# Grove_-_Joint_v2_0.net
KiCad netlist of a schematic drawn in EAGLE
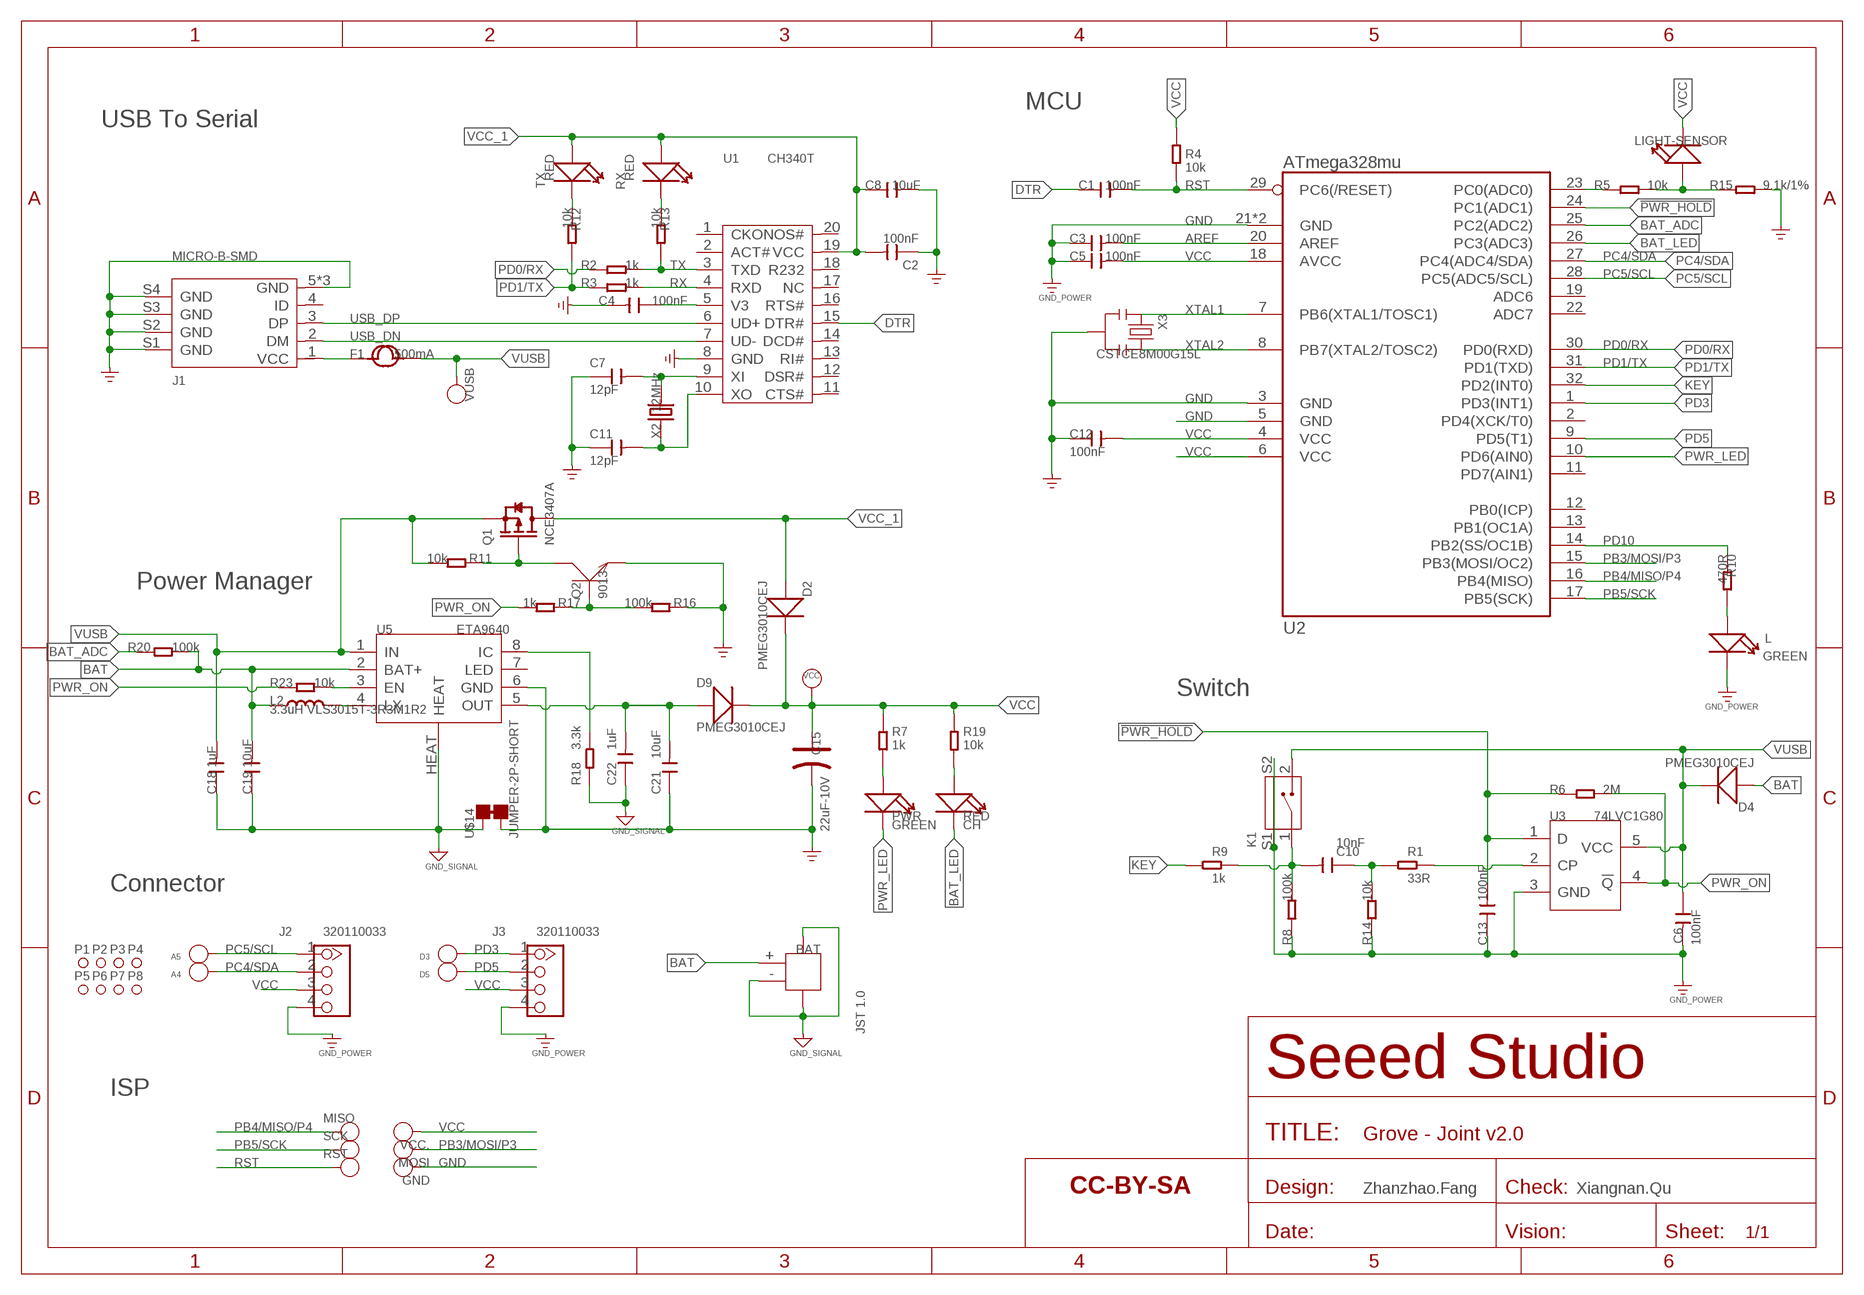
[diagram p0: schematic, sheet 1]

(export (version "E")
  (design (tool "Eeschema 10.0.6"))
  (components
    (comp (ref "A4")
      (value "DNP")
      (footprint "eagle-import:TP_4545")
      (libsource (lib "eagle-import") (part "PAD-TEST-POINT'4545'"))
    )
    (comp (ref "A5")
      (value "DNP")
      (footprint "eagle-import:TP_4545")
      (libsource (lib "eagle-import") (part "PAD-TEST-POINT'4545'"))
    )
    (comp (ref "BAT")
      (value "JST 1.0")
      (footprint "eagle-import:2P-SMD-1.0")
      (libsource (lib "eagle-import") (part "JST-2P-SMD'1.0'"))
    )
    (comp (ref "C1")
      (value "100nF")
      (footprint "eagle-import:C0402")
      (libsource (lib "eagle-import") (part "CAP-0402"))
    )
    (comp (ref "C2")
      (value "100nF")
      (footprint "eagle-import:C0402")
      (libsource (lib "eagle-import") (part "CAP-0402"))
    )
    (comp (ref "C3")
      (value "100nF")
      (footprint "eagle-import:C0402")
      (libsource (lib "eagle-import") (part "CAP-0402"))
    )
    (comp (ref "C4")
      (value "100nF")
      (footprint "eagle-import:C0402")
      (libsource (lib "eagle-import") (part "CAP-0402"))
    )
    (comp (ref "C5")
      (value "100nF")
      (footprint "eagle-import:C0402")
      (libsource (lib "eagle-import") (part "CAP-0402"))
    )
    (comp (ref "C6")
      (value "100nF")
      (footprint "eagle-import:C0402")
      (libsource (lib "eagle-import") (part "CAP-0402"))
    )
    (comp (ref "C7")
      (value "12pF")
      (footprint "eagle-import:C0402")
      (libsource (lib "eagle-import") (part "CAP-0402"))
    )
    (comp (ref "C8")
      (value "10uF")
      (footprint "eagle-import:C0805")
      (libsource (lib "eagle-import") (part "CAP-0805"))
    )
    (comp (ref "C10")
      (value "10nF")
      (footprint "eagle-import:C0402")
      (libsource (lib "eagle-import") (part "CAP-0402"))
    )
    (comp (ref "C11")
      (value "12pF")
      (footprint "eagle-import:C0402")
      (libsource (lib "eagle-import") (part "CAP-0402"))
    )
    (comp (ref "C12")
      (value "100nF")
      (footprint "eagle-import:C0402")
      (libsource (lib "eagle-import") (part "CAP-0402"))
    )
    (comp (ref "C13")
      (value "100nF")
      (footprint "eagle-import:C0402")
      (libsource (lib "eagle-import") (part "CAP-0402"))
    )
    (comp (ref "C15")
      (value "22uF-10V")
      (footprint "eagle-import:AVX-A")
      (libsource (lib "eagle-import") (part "CAP-POLAR-AVX-A"))
    )
    (comp (ref "C18")
      (value "1uF")
      (footprint "eagle-import:C0805")
      (libsource (lib "eagle-import") (part "CAP-0805"))
    )
    (comp (ref "C19")
      (value "10uF")
      (footprint "eagle-import:C0805")
      (libsource (lib "eagle-import") (part "CAP-0805"))
    )
    (comp (ref "C21")
      (value "10uF")
      (footprint "eagle-import:C0805")
      (libsource (lib "eagle-import") (part "CAP-0805"))
    )
    (comp (ref "C22")
      (value "1uF")
      (footprint "eagle-import:C0603")
      (libsource (lib "eagle-import") (part "CAP-0603"))
    )
    (comp (ref "CH")
      (value "RED")
      (footprint "eagle-import:LED-0402")
      (libsource (lib "eagle-import") (part "LED'0402'"))
    )
    (comp (ref "D2")
      (value "PMEG3010CEJ")
      (footprint "eagle-import:SOD-323")
      (libsource (lib "eagle-import") (part "DIODE'0805'"))
    )
    (comp (ref "D3")
      (value "DNP")
      (footprint "eagle-import:TP-D45MIL")
      (libsource (lib "eagle-import") (part "Discrete-new_PAD-TEST-POINT'4545'"))
    )
    (comp (ref "D4")
      (value "PMEG3010CEJ")
      (footprint "eagle-import:SOD-323")
      (libsource (lib "eagle-import") (part "DIODE'0805'"))
    )
    (comp (ref "D5")
      (value "DNP")
      (footprint "eagle-import:TP_4545")
      (libsource (lib "eagle-import") (part "PAD-TEST-POINT'4545'"))
    )
    (comp (ref "D9")
      (value "PMEG3010CEJ")
      (footprint "eagle-import:SOD-323")
      (libsource (lib "eagle-import") (part "DIODE'0805'"))
    )
    (comp (ref "F1")
      (value "500mA")
      (footprint "eagle-import:F1206")
      (libsource (lib "eagle-import") (part "FUSE'1206'"))
    )
    (comp (ref "GND")
      (value "DNP")
      (footprint "eagle-import:TP-D45MIL")
      (libsource (lib "eagle-import") (part "Discrete-new_PAD-TEST-POINT'4545'"))
    )
    (comp (ref "J1")
      (value "MICRO-B-SMD")
      (footprint "eagle-import:5+4P-SMD-0.65-B")
      (libsource (lib "eagle-import") (part "USB-MICRO-5P'5+4P'"))
    )
    (comp (ref "J2")
      (value "320110033")
      (footprint "eagle-import:4P-2.0")
      (libsource (lib "eagle-import") (part "GROVE-CONNECTOR-DIP-2.0"))
    )
    (comp (ref "J3")
      (value "320110033")
      (footprint "eagle-import:4P-2.0")
      (libsource (lib "eagle-import") (part "GROVE-CONNECTOR-DIP-2.0"))
    )
    (comp (ref "K1")
      (value "311020023")
      (footprint "eagle-import:4P-SMD-L7.0_W3.5_H3.5MM-90D")
      (libsource (lib "eagle-import") (part "BUTTON-2+2P'TS-1188E'"))
    )
    (comp (ref "L")
      (value "GREEN")
      (footprint "eagle-import:LED-0402")
      (libsource (lib "eagle-import") (part "LED'0402'"))
    )
    (comp (ref "L2")
      (value "3.3uH VLS3015T-3R3M1R2")
      (footprint "eagle-import:L3015")
      (libsource (lib "eagle-import") (part "L'SLW3015S220MST'"))
    )
    (comp (ref "LIGHT-SENSOR")
      (value "light_sensor")
      (footprint "eagle-import:LED-0805")
      (libsource (lib "eagle-import") (part "LED'0805'"))
    )
    (comp (ref "MISO")
      (value "DNP")
      (footprint "eagle-import:TP-D45MIL")
      (libsource (lib "eagle-import") (part "Discrete-new_PAD-TEST-POINT'4545'"))
    )
    (comp (ref "MOSI")
      (value "DNP")
      (footprint "eagle-import:TP-D45MIL")
      (libsource (lib "eagle-import") (part "Discrete-new_PAD-TEST-POINT'4545'"))
    )
    (comp (ref "P1")
      (value "PAD-MARK'ANNULAR'")
      (footprint "eagle-import:ROUND-MARK-1.0")
      (fields (field (name "PARTNO") "DNP"))
      (libsource (lib "eagle-import") (part "PAD-MARK'ANNULAR'"))
    )
    (comp (ref "P2")
      (value "PAD-MARK'ANNULAR'")
      (footprint "eagle-import:ROUND-MARK-1.0")
      (fields (field (name "PARTNO") "DNP"))
      (libsource (lib "eagle-import") (part "PAD-MARK'ANNULAR'"))
    )
    (comp (ref "P3")
      (value "PAD-MARK'ANNULAR'")
      (footprint "eagle-import:ROUND-MARK-1.0")
      (fields (field (name "PARTNO") "DNP"))
      (libsource (lib "eagle-import") (part "PAD-MARK'ANNULAR'"))
    )
    (comp (ref "P4")
      (value "PAD-MARK'ANNULAR'")
      (footprint "eagle-import:ROUND-MARK-1.0")
      (fields (field (name "PARTNO") "DNP"))
      (libsource (lib "eagle-import") (part "PAD-MARK'ANNULAR'"))
    )
    (comp (ref "P5")
      (value "PAD-MARK'ANNULAR'")
      (footprint "eagle-import:ROUND-MARK-1.0")
      (fields (field (name "PARTNO") "DNP"))
      (libsource (lib "eagle-import") (part "PAD-MARK'ANNULAR'"))
    )
    (comp (ref "P6")
      (value "PAD-MARK'ANNULAR'")
      (footprint "eagle-import:ROUND-MARK-1.0")
      (fields (field (name "PARTNO") "DNP"))
      (libsource (lib "eagle-import") (part "PAD-MARK'ANNULAR'"))
    )
    (comp (ref "P7")
      (value "PAD-MARK'ANNULAR'")
      (footprint "eagle-import:ROUND-MARK-1.0")
      (fields (field (name "PARTNO") "DNP"))
      (libsource (lib "eagle-import") (part "PAD-MARK'ANNULAR'"))
    )
    (comp (ref "P8")
      (value "PAD-MARK'ANNULAR'")
      (footprint "eagle-import:ROUND-MARK-1.0")
      (fields (field (name "PARTNO") "DNP"))
      (libsource (lib "eagle-import") (part "PAD-MARK'ANNULAR'"))
    )
    (comp (ref "PWR")
      (value "GREEN")
      (footprint "eagle-import:LED-0402")
      (libsource (lib "eagle-import") (part "LED'0402'"))
    )
    (comp (ref "Q1")
      (value "NCE3407A")
      (footprint "eagle-import:SOT-23")
      (libsource (lib "eagle-import") (part "MOSFET-P'SI2323CDS/SI2305DS{lt}BR{gt}'"))
    )
    (comp (ref "Q2")
      (value "9013")
      (footprint "eagle-import:SOT-323")
      (libsource (lib "eagle-import") (part "TRANSISTOR-NPN-SOT323"))
    )
    (comp (ref "R1")
      (value "33R")
      (footprint "eagle-import:R0402")
      (libsource (lib "eagle-import") (part "RES-0402"))
    )
    (comp (ref "R2")
      (value "1k")
      (footprint "eagle-import:R0402")
      (libsource (lib "eagle-import") (part "RES-0402"))
    )
    (comp (ref "R3")
      (value "1k")
      (footprint "eagle-import:R0402")
      (libsource (lib "eagle-import") (part "RES-0402"))
    )
    (comp (ref "R4")
      (value "10k")
      (footprint "eagle-import:R0402")
      (libsource (lib "eagle-import") (part "RES-0402"))
    )
    (comp (ref "R5")
      (value "10k")
      (footprint "eagle-import:R0402")
      (libsource (lib "eagle-import") (part "RES-0402"))
    )
    (comp (ref "R6")
      (value "2M")
      (footprint "eagle-import:R0402")
      (libsource (lib "eagle-import") (part "RES-0402"))
    )
    (comp (ref "R7")
      (value "1k")
      (footprint "eagle-import:R0402")
      (libsource (lib "eagle-import") (part "RES-0402"))
    )
    (comp (ref "R8")
      (value "100k")
      (footprint "eagle-import:R0402")
      (libsource (lib "eagle-import") (part "RES-0402"))
    )
    (comp (ref "R9")
      (value "1k")
      (footprint "eagle-import:R0402")
      (libsource (lib "eagle-import") (part "RES-0402"))
    )
    (comp (ref "R10")
      (value "470R")
      (footprint "eagle-import:R0402")
      (libsource (lib "eagle-import") (part "RES-0402"))
    )
    (comp (ref "R11")
      (value "10k")
      (footprint "eagle-import:R0402")
      (libsource (lib "eagle-import") (part "RES-0402"))
    )
    (comp (ref "R12")
      (value "10k")
      (footprint "eagle-import:R0402")
      (libsource (lib "eagle-import") (part "RES-0402"))
    )
    (comp (ref "R13")
      (value "10k")
      (footprint "eagle-import:R0402")
      (libsource (lib "eagle-import") (part "RES-0402"))
    )
    (comp (ref "R14")
      (value "10k")
      (footprint "eagle-import:R0402")
      (libsource (lib "eagle-import") (part "RES-0402"))
    )
    (comp (ref "R15")
      (value "9.1k/1%")
      (footprint "eagle-import:R0402")
      (libsource (lib "eagle-import") (part "RES-0402"))
    )
    (comp (ref "R16")
      (value "100k")
      (footprint "eagle-import:R0402")
      (libsource (lib "eagle-import") (part "RES-0402"))
    )
    (comp (ref "R17")
      (value "1k")
      (footprint "eagle-import:R0402")
      (libsource (lib "eagle-import") (part "RES-0402"))
    )
    (comp (ref "R18")
      (value "3.3k")
      (footprint "eagle-import:R0402")
      (libsource (lib "eagle-import") (part "RES-0402"))
    )
    (comp (ref "R19")
      (value "10k")
      (footprint "eagle-import:R0402")
      (libsource (lib "eagle-import") (part "RES-0402"))
    )
    (comp (ref "R20")
      (value "100k")
      (footprint "eagle-import:R0402")
      (libsource (lib "eagle-import") (part "RES-0402"))
    )
    (comp (ref "R23")
      (value "10k")
      (footprint "eagle-import:R0402")
      (libsource (lib "eagle-import") (part "RES-0402"))
    )
    (comp (ref "RST")
      (value "DNP")
      (footprint "eagle-import:TP-D45MIL")
      (libsource (lib "eagle-import") (part "Discrete-new_PAD-TEST-POINT'4545'"))
    )
    (comp (ref "RX")
      (value "RED")
      (footprint "eagle-import:LED-0402")
      (libsource (lib "eagle-import") (part "LED'0402'"))
    )
    (comp (ref "SCK")
      (value "DNP")
      (footprint "eagle-import:TP-D45MIL")
      (libsource (lib "eagle-import") (part "Discrete-new_PAD-TEST-POINT'4545'"))
    )
    (comp (ref "TX")
      (value "RED")
      (footprint "eagle-import:LED-0402")
      (libsource (lib "eagle-import") (part "LED'0402'"))
    )
    (comp (ref "U$4")
      (value "SEEEDSTUDIO-OPEN-SCH-FRAME")
      (footprint "eagle-import:SEEEDSTUDIO-PCB-FRAME")
      (libsource (lib "eagle-import") (part "SEEEDSTUDIO-OPEN-SCH-FRAME"))
    )
    (comp (ref "U$14")
      (value "JUMPER-2P-SHORT")
      (footprint "eagle-import:2P-SMD-SHORT")
      (libsource (lib "eagle-import") (part "JUMPER-2P-SHORT"))
    )
    (comp (ref "U1")
      (value "CH340T")
      (footprint "eagle-import:SSOP20")
      (libsource (lib "eagle-import") (part "CH340T"))
    )
    (comp (ref "U2")
      (value "ATmega328mu")
      (footprint "eagle-import:MLF32X-W_HEAT")
      (libsource (lib "eagle-import") (part "ATMEGA8/168/328MLF"))
    )
    (comp (ref "U3")
      (value "74LVC1G80")
      (footprint "eagle-import:SOT-753")
      (libsource (lib "eagle-import") (part "74LVC1G80"))
    )
    (comp (ref "U5")
      (value "ETA9640")
      (footprint "eagle-import:SOP8-W_HEAT")
      (libsource (lib "eagle-import") (part "ETA9640"))
    )
    (comp (ref "VCC")
      (value "NC")
      (footprint "eagle-import:TP-D45MIL")
      (fields (field (name "PARTNO") "DNP"))
      (libsource (lib "eagle-import") (part "Discrete-new_PAD-TEST-POINT'4545'"))
    )
    (comp (ref "VCC.")
      (value "NC")
      (footprint "eagle-import:TP-D45MIL")
      (fields (field (name "PARTNO") "DNP"))
      (libsource (lib "eagle-import") (part "Discrete-new_PAD-TEST-POINT'4545'"))
    )
    (comp (ref "VUSB")
      (value "PAD-TEST-POINT'4545'")
      (footprint "eagle-import:TP-D45MIL")
      (fields (field (name "PARTNO") "DNP"))
      (libsource (lib "eagle-import") (part "Discrete-new_PAD-TEST-POINT'4545'"))
    )
    (comp (ref "X2")
      (value "12MHz")
      (footprint "eagle-import:2P-SMD-L5.0XW3.2MM")
      (libsource (lib "eagle-import") (part "CRYSTAL'5032'"))
    )
    (comp (ref "X3")
      (value "CSTCE8M00G15L")
      (footprint "eagle-import:3P-SMD-L3.6_W1.3MM")
      (libsource (lib "eagle-import") (part "CRYSTAL-RESONATOR'SMD'"))
    )
  )
  (nets
    (net (code "1") (name "/AREF") (class "Default")
      (node (ref "C3") (pin "2") (pinfunction "2_2") (pintype "passive"))
      (node (ref "U2") (pin "20") (pinfunction "AREF_20") (pintype "bidirectional"))
    )
    (net (code "2") (name "/NOS#") (class "Default")
      (node (ref "U1") (pin "20") (pinfunction "NOS#_20") (pintype "power_in"))
    )
    (net (code "3") (name "/PB3{slash}MOSI{slash}P3") (class "Default")
      (node (ref "MOSI") (pin "T") (pinfunction "T_T") (pintype "bidirectional"))
      (node (ref "U2") (pin "15") (pinfunction "PB3(MOSI/OC2)_15") (pintype "bidirectional"))
    )
    (net (code "4") (name "/PB4{slash}MISO{slash}P4") (class "Default")
      (node (ref "MISO") (pin "T") (pinfunction "T_T") (pintype "bidirectional"))
      (node (ref "U2") (pin "16") (pinfunction "PB4(MISO)_16") (pintype "bidirectional"))
    )
    (net (code "5") (name "/PB5{slash}SCK") (class "Default")
      (node (ref "SCK") (pin "T") (pinfunction "T_T") (pintype "bidirectional"))
      (node (ref "U2") (pin "17") (pinfunction "PB5(SCK)_17") (pintype "bidirectional"))
    )
    (net (code "6") (name "/PD10") (class "Default")
      (node (ref "R10") (pin "1") (pinfunction "1_1") (pintype "passive"))
      (node (ref "U2") (pin "14") (pinfunction "PB2(SS/OC1B)_14") (pintype "bidirectional"))
    )
    (net (code "7") (name "/RST") (class "Default")
      (node (ref "C1") (pin "2") (pinfunction "2_2") (pintype "passive"))
      (node (ref "R4") (pin "1") (pinfunction "1_1") (pintype "passive"))
      (node (ref "RST") (pin "T") (pinfunction "T_T") (pintype "bidirectional"))
      (node (ref "U2") (pin "29") (pinfunction "PC6(/RESET)_29") (pintype "bidirectional"))
    )
    (net (code "8") (name "/RX") (class "Default")
      (node (ref "R3") (pin "2") (pinfunction "2_2") (pintype "passive"))
      (node (ref "U1") (pin "4") (pinfunction "RXD_4") (pintype "input"))
    )
    (net (code "9") (name "/TX") (class "Default")
      (node (ref "R13") (pin "2") (pinfunction "2_2") (pintype "passive"))
      (node (ref "R2") (pin "2") (pinfunction "2_2") (pintype "passive"))
      (node (ref "U1") (pin "3") (pinfunction "TXD_3") (pintype "output"))
    )
    (net (code "10") (name "/USB_DN") (class "Default")
      (node (ref "J1") (pin "2") (pinfunction "DM_2") (pintype "bidirectional"))
      (node (ref "U1") (pin "7") (pinfunction "UD-_7") (pintype "bidirectional"))
    )
    (net (code "11") (name "/USB_DP") (class "Default")
      (node (ref "J1") (pin "3") (pinfunction "DP_3") (pintype "bidirectional"))
      (node (ref "U1") (pin "6") (pinfunction "UD+_6") (pintype "bidirectional"))
    )
    (net (code "12") (name "/XTAL1") (class "Default")
      (node (ref "U2") (pin "7") (pinfunction "PB6(XTAL1/TOSC1)_7") (pintype "bidirectional"))
      (node (ref "X3") (pin "1") (pinfunction "1_1") (pintype "passive"))
    )
    (net (code "13") (name "/XTAL2") (class "Default")
      (node (ref "U2") (pin "8") (pinfunction "PB7(XTAL2/TOSC2)_8") (pintype "bidirectional"))
      (node (ref "X3") (pin "3") (pinfunction "3_3") (pintype "passive"))
    )
    (net (code "14") (name "/~{PWR_HOLD}") (class "Default")
      (node (ref "C13") (pin "2") (pinfunction "2_2") (pintype "passive"))
      (node (ref "R6") (pin "1") (pinfunction "1_1") (pintype "passive"))
      (node (ref "U2") (pin "24") (pinfunction "PC1(ADC1)_24") (pintype "bidirectional"))
      (node (ref "U3") (pin "1") (pinfunction "D_1") (pintype "bidirectional"))
    )
    (net (code "15") (name "BAT") (class "Default")
      (node (ref "BAT") (pin "+") (pinfunction "1_+") (pintype "bidirectional"))
      (node (ref "C19") (pin "2") (pinfunction "2_2") (pintype "passive"))
      (node (ref "D4") (pin "+") (pinfunction "+_+") (pintype "passive"))
      (node (ref "L2") (pin "1") (pinfunction "1_1") (pintype "passive"))
      (node (ref "R20") (pin "2") (pinfunction "2_2") (pintype "passive"))
      (node (ref "U5") (pin "2") (pinfunction "BAT+_2") (pintype "bidirectional"))
    )
    (net (code "16") (name "BAT_ADC") (class "Default")
      (node (ref "R20") (pin "1") (pinfunction "1_1") (pintype "passive"))
      (node (ref "U2") (pin "25") (pinfunction "PC2(ADC2)_25") (pintype "bidirectional"))
    )
    (net (code "17") (name "BAT_LED") (class "Default")
      (node (ref "CH") (pin "-") (pinfunction "-_-") (pintype "passive"))
      (node (ref "U2") (pin "26") (pinfunction "PC3(ADC3)_26") (pintype "bidirectional"))
    )
    (net (code "18") (name "DTR") (class "Default")
      (node (ref "C1") (pin "1") (pinfunction "1_1") (pintype "passive"))
      (node (ref "U1") (pin "15") (pinfunction "DTR#_15") (pintype "output"))
    )
    (net (code "19") (name "GND") (class "Default")
      (node (ref "C11") (pin "1") (pinfunction "1_1") (pintype "passive"))
      (node (ref "C12") (pin "1") (pinfunction "1_1") (pintype "passive"))
      (node (ref "C13") (pin "1") (pinfunction "1_1") (pintype "passive"))
      (node (ref "C15") (pin "-") (pinfunction "-_-") (pintype "passive"))
      (node (ref "C2") (pin "1") (pinfunction "1_1") (pintype "passive"))
      (node (ref "C21") (pin "1") (pinfunction "1_1") (pintype "passive"))
      (node (ref "C3") (pin "1") (pinfunction "1_1") (pintype "passive"))
      (node (ref "C4") (pin "2") (pinfunction "2_2") (pintype "passive"))
      (node (ref "C5") (pin "1") (pinfunction "1_1") (pintype "passive"))
      (node (ref "C6") (pin "2") (pinfunction "2_2") (pintype "passive"))
      (node (ref "C7") (pin "1") (pinfunction "1_1") (pintype "passive"))
      (node (ref "C8") (pin "2") (pinfunction "2_2") (pintype "passive"))
      (node (ref "GND") (pin "T") (pinfunction "T_T") (pintype "bidirectional"))
      (node (ref "J1") (pin "5") (pinfunction "GND_5") (pintype "bidirectional"))
      (node (ref "J1") (pin "S1") (pinfunction "GND_S1") (pintype "bidirectional"))
      (node (ref "J1") (pin "S2") (pinfunction "GND_S2") (pintype "bidirectional"))
      (node (ref "J1") (pin "S3") (pinfunction "GND_S3") (pintype "bidirectional"))
      (node (ref "J1") (pin "S4") (pinfunction "GND_S4") (pintype "bidirectional"))
      (node (ref "J1") (pin "S5") (pinfunction "GND_S5") (pintype "bidirectional"))
      (node (ref "J1") (pin "S6") (pinfunction "GND_S6") (pintype "bidirectional"))
      (node (ref "J2") (pin "4") (pinfunction "4_4") (pintype "bidirectional"))
      (node (ref "J3") (pin "4") (pinfunction "4_4") (pintype "bidirectional"))
      (node (ref "K1") (pin "S1") (pinfunction "S1_S1") (pintype "bidirectional"))
      (node (ref "K1") (pin "S2") (pinfunction "S2_S2") (pintype "bidirectional"))
      (node (ref "L") (pin "-") (pinfunction "-_-") (pintype "passive"))
      (node (ref "Q2") (pin "2") (pinfunction "E_2") (pintype "passive"))
      (node (ref "R14") (pin "1") (pinfunction "1_1") (pintype "passive"))
      (node (ref "R15") (pin "2") (pinfunction "2_2") (pintype "passive"))
      (node (ref "R16") (pin "2") (pinfunction "2_2") (pintype "passive"))
      (node (ref "R8") (pin "1") (pinfunction "1_1") (pintype "passive"))
      (node (ref "U$14") (pin "2") (pinfunction "2_2") (pintype "bidirectional"))
      (node (ref "U1") (pin "8") (pinfunction "GND_8") (pintype "power_in"))
      (node (ref "U2") (pin "21") (pinfunction "GND_21") (pintype "bidirectional"))
      (node (ref "U2") (pin "3") (pinfunction "GND_3") (pintype "bidirectional"))
      (node (ref "U2") (pin "5") (pinfunction "GND_5") (pintype "bidirectional"))
      (node (ref "U2") (pin "HEAT") (pinfunction "GND_HEAT") (pintype "bidirectional"))
      (node (ref "U3") (pin "3") (pinfunction "GND_3") (pintype "bidirectional"))
      (node (ref "U5") (pin "6") (pinfunction "GND_6") (pintype "bidirectional"))
      (node (ref "X3") (pin "2") (pinfunction "2_2") (pintype "passive"))
    )
    (net (code "20") (name "GND_SIGNAL") (class "Default")
      (node (ref "BAT") (pin "-") (pinfunction "2_-") (pintype "bidirectional"))
      (node (ref "BAT") (pin "3") (pinfunction "3_3") (pintype "bidirectional"))
      (node (ref "BAT") (pin "4") (pinfunction "4_4") (pintype "bidirectional"))
      (node (ref "C18") (pin "1") (pinfunction "1_1") (pintype "passive"))
      (node (ref "C19") (pin "1") (pinfunction "1_1") (pintype "passive"))
      (node (ref "C22") (pin "1") (pinfunction "1_1") (pintype "passive"))
      (node (ref "R18") (pin "2") (pinfunction "2_2") (pintype "passive"))
      (node (ref "U$14") (pin "1") (pinfunction "1_1") (pintype "bidirectional"))
      (node (ref "U5") (pin "HEAT") (pinfunction "HEAT_HEAT") (pintype "bidirectional"))
    )
    (net (code "21") (name "KEY") (class "Default")
      (node (ref "R9") (pin "1") (pinfunction "1_1") (pintype "passive"))
      (node (ref "U2") (pin "32") (pinfunction "PD2(INT0)_32") (pintype "bidirectional"))
    )
    (net (code "22") (name "Net-(C10-Pad1)") (class "Default")
      (node (ref "C10") (pin "1") (pinfunction "1_1") (pintype "passive"))
      (node (ref "R1") (pin "1") (pinfunction "1_1") (pintype "passive"))
      (node (ref "R14") (pin "2") (pinfunction "2_2") (pintype "passive"))
    )
    (net (code "23") (name "Net-(C10-Pad2)") (class "Default")
      (node (ref "C10") (pin "2") (pinfunction "2_2") (pintype "passive"))
      (node (ref "K1") (pin "1") (pinfunction "1_1") (pintype "bidirectional"))
      (node (ref "R8") (pin "2") (pinfunction "2_2") (pintype "passive"))
      (node (ref "R9") (pin "2") (pinfunction "2_2") (pintype "passive"))
    )
    (net (code "24") (name "Net-(CH-Pad+)") (class "Default")
      (node (ref "CH") (pin "+") (pinfunction "+_+") (pintype "passive"))
      (node (ref "R19") (pin "1") (pinfunction "1_1") (pintype "passive"))
    )
    (net (code "25") (name "Net-(J1-VCC)") (class "Default")
      (node (ref "F1") (pin "1") (pinfunction "1_1") (pintype "bidirectional"))
      (node (ref "J1") (pin "1") (pinfunction "VCC_1") (pintype "bidirectional"))
    )
    (net (code "26") (name "Net-(L-Pad+)") (class "Default")
      (node (ref "L") (pin "+") (pinfunction "+_+") (pintype "passive"))
      (node (ref "R10") (pin "2") (pinfunction "2_2") (pintype "passive"))
    )
    (net (code "27") (name "Net-(LIGHT-SENSOR-Pad+)") (class "Default")
      (node (ref "LIGHT-SENSOR") (pin "+") (pinfunction "+_+") (pintype "passive"))
      (node (ref "R15") (pin "1") (pinfunction "1_1") (pintype "passive"))
      (node (ref "R5") (pin "2") (pinfunction "2_2") (pintype "passive"))
    )
    (net (code "28") (name "Net-(PWR-Pad+)") (class "Default")
      (node (ref "PWR") (pin "+") (pinfunction "+_+") (pintype "passive"))
      (node (ref "R7") (pin "2") (pinfunction "2_2") (pintype "passive"))
    )
    (net (code "29") (name "Net-(Q1-G)") (class "Default")
      (node (ref "Q1") (pin "1") (pinfunction "G_1") (pintype "passive"))
      (node (ref "Q2") (pin "3") (pinfunction "C_3") (pintype "passive"))
      (node (ref "R11") (pin "2") (pinfunction "2_2") (pintype "passive"))
    )
    (net (code "30") (name "Net-(Q2-B)") (class "Default")
      (node (ref "Q2") (pin "1") (pinfunction "B_1") (pintype "passive"))
      (node (ref "R16") (pin "1") (pinfunction "1_1") (pintype "passive"))
      (node (ref "R17") (pin "2") (pinfunction "2_2") (pintype "passive"))
    )
    (net (code "31") (name "Net-(R12-Pad1)") (class "Default")
      (node (ref "R12") (pin "1") (pinfunction "1_1") (pintype "passive"))
      (node (ref "TX") (pin "-") (pinfunction "-_-") (pintype "passive"))
    )
    (net (code "32") (name "Net-(R13-Pad1)") (class "Default")
      (node (ref "R13") (pin "1") (pinfunction "1_1") (pintype "passive"))
      (node (ref "RX") (pin "-") (pinfunction "-_-") (pintype "passive"))
    )
    (net (code "33") (name "Net-(U1-V3)") (class "Default")
      (node (ref "C4") (pin "1") (pinfunction "1_1") (pintype "passive"))
      (node (ref "U1") (pin "5") (pinfunction "V3_5") (pintype "power_in"))
    )
    (net (code "34") (name "Net-(U1-XI)") (class "Default")
      (node (ref "C7") (pin "2") (pinfunction "2_2") (pintype "passive"))
      (node (ref "U1") (pin "9") (pinfunction "XI_9") (pintype "input"))
      (node (ref "X2") (pin "2") (pinfunction "2_2") (pintype "passive"))
    )
    (net (code "35") (name "Net-(U1-XO)") (class "Default")
      (node (ref "C11") (pin "2") (pinfunction "2_2") (pintype "passive"))
      (node (ref "U1") (pin "10") (pinfunction "XO_10") (pintype "output"))
      (node (ref "X2") (pin "1") (pinfunction "1_1") (pintype "passive"))
    )
    (net (code "36") (name "Net-(U2-PC0(ADC0))") (class "Default")
      (node (ref "R5") (pin "1") (pinfunction "1_1") (pintype "passive"))
      (node (ref "U2") (pin "23") (pinfunction "PC0(ADC0)_23") (pintype "bidirectional"))
    )
    (net (code "37") (name "Net-(U3-CP)") (class "Default")
      (node (ref "R1") (pin "2") (pinfunction "2_2") (pintype "passive"))
      (node (ref "U3") (pin "2") (pinfunction "CP_2") (pintype "bidirectional"))
    )
    (net (code "38") (name "Net-(U5-EN)") (class "Default")
      (node (ref "R23") (pin "2") (pinfunction "2_2") (pintype "passive"))
      (node (ref "U5") (pin "3") (pinfunction "EN_3") (pintype "bidirectional"))
    )
    (net (code "39") (name "Net-(U5-IC)") (class "Default")
      (node (ref "R18") (pin "1") (pinfunction "1_1") (pintype "passive"))
      (node (ref "U5") (pin "8") (pinfunction "IC_8") (pintype "bidirectional"))
    )
    (net (code "40") (name "Net-(U5-LX)") (class "Default")
      (node (ref "L2") (pin "2") (pinfunction "2_2") (pintype "passive"))
      (node (ref "U5") (pin "4") (pinfunction "LX_4") (pintype "bidirectional"))
    )
    (net (code "41") (name "Net-(U5-OUT)") (class "Default")
      (node (ref "C21") (pin "2") (pinfunction "2_2") (pintype "passive"))
      (node (ref "C22") (pin "2") (pinfunction "2_2") (pintype "passive"))
      (node (ref "D9") (pin "+") (pinfunction "+_+") (pintype "passive"))
      (node (ref "U5") (pin "5") (pinfunction "OUT_5") (pintype "bidirectional"))
    )
    (net (code "42") (name "PC4{slash}SDA") (class "Default")
      (node (ref "A4") (pin "T") (pinfunction "T_T") (pintype "bidirectional"))
      (node (ref "J2") (pin "2") (pinfunction "2_2") (pintype "bidirectional"))
      (node (ref "U2") (pin "27") (pinfunction "PC4(ADC4/SDA)_27") (pintype "bidirectional"))
    )
    (net (code "43") (name "PC5{slash}SCL") (class "Default")
      (node (ref "A5") (pin "T") (pinfunction "T_T") (pintype "bidirectional"))
      (node (ref "J2") (pin "1") (pinfunction "1_1") (pintype "bidirectional"))
      (node (ref "U2") (pin "28") (pinfunction "PC5(ADC5/SCL)_28") (pintype "bidirectional"))
    )
    (net (code "44") (name "PD0{slash}RX") (class "Default")
      (node (ref "R2") (pin "1") (pinfunction "1_1") (pintype "passive"))
      (node (ref "U2") (pin "30") (pinfunction "PD0(RXD)_30") (pintype "bidirectional"))
    )
    (net (code "45") (name "PD1{slash}TX") (class "Default")
      (node (ref "R12") (pin "2") (pinfunction "2_2") (pintype "passive"))
      (node (ref "R3") (pin "1") (pinfunction "1_1") (pintype "passive"))
      (node (ref "U2") (pin "31") (pinfunction "PD1(TXD)_31") (pintype "bidirectional"))
    )
    (net (code "46") (name "PD3") (class "Default")
      (node (ref "D3") (pin "T") (pinfunction "T_T") (pintype "bidirectional"))
      (node (ref "J3") (pin "1") (pinfunction "1_1") (pintype "bidirectional"))
      (node (ref "U2") (pin "1") (pinfunction "PD3(INT1)_1") (pintype "bidirectional"))
    )
    (net (code "47") (name "PD5") (class "Default")
      (node (ref "D5") (pin "T") (pinfunction "T_T") (pintype "bidirectional"))
      (node (ref "J3") (pin "2") (pinfunction "2_2") (pintype "bidirectional"))
      (node (ref "U2") (pin "9") (pinfunction "PD5(T1)_9") (pintype "bidirectional"))
    )
    (net (code "48") (name "PWR_LED") (class "Default")
      (node (ref "PWR") (pin "-") (pinfunction "-_-") (pintype "passive"))
      (node (ref "U2") (pin "10") (pinfunction "PD6(AIN0)_10") (pintype "bidirectional"))
    )
    (net (code "49") (name "PWR_ON") (class "Default")
      (node (ref "R17") (pin "1") (pinfunction "1_1") (pintype "passive"))
      (node (ref "R23") (pin "1") (pinfunction "1_1") (pintype "passive"))
      (node (ref "R6") (pin "2") (pinfunction "2_2") (pintype "passive"))
      (node (ref "U3") (pin "4") (pinfunction "~{Q}_4") (pintype "bidirectional"))
    )
    (net (code "50") (name "VCC") (class "Default")
      (node (ref "C12") (pin "2") (pinfunction "2_2") (pintype "passive"))
      (node (ref "C15") (pin "+") (pinfunction "+_+") (pintype "passive"))
      (node (ref "C5") (pin "2") (pinfunction "2_2") (pintype "passive"))
      (node (ref "D2") (pin "-") (pinfunction "-_-") (pintype "passive"))
      (node (ref "D9") (pin "-") (pinfunction "-_-") (pintype "passive"))
      (node (ref "J2") (pin "3") (pinfunction "3_3") (pintype "bidirectional"))
      (node (ref "J3") (pin "3") (pinfunction "3_3") (pintype "bidirectional"))
      (node (ref "LIGHT-SENSOR") (pin "-") (pinfunction "-_-") (pintype "passive"))
      (node (ref "R19") (pin "2") (pinfunction "2_2") (pintype "passive"))
      (node (ref "R4") (pin "2") (pinfunction "2_2") (pintype "passive"))
      (node (ref "R7") (pin "1") (pinfunction "1_1") (pintype "passive"))
      (node (ref "U2") (pin "18") (pinfunction "AVCC_18") (pintype "bidirectional"))
      (node (ref "U2") (pin "4") (pinfunction "VCC_4") (pintype "bidirectional"))
      (node (ref "U2") (pin "6") (pinfunction "VCC_6") (pintype "bidirectional"))
      (node (ref "VCC") (pin "T") (pinfunction "T_T") (pintype "bidirectional"))
      (node (ref "VCC.") (pin "T") (pinfunction "T_T") (pintype "bidirectional"))
    )
    (net (code "51") (name "VCC_1") (class "Default")
      (node (ref "C2") (pin "2") (pinfunction "2_2") (pintype "passive"))
      (node (ref "C8") (pin "1") (pinfunction "1_1") (pintype "passive"))
      (node (ref "D2") (pin "+") (pinfunction "+_+") (pintype "passive"))
      (node (ref "Q1") (pin "3") (pinfunction "D_3") (pintype "passive"))
      (node (ref "RX") (pin "+") (pinfunction "+_+") (pintype "passive"))
      (node (ref "TX") (pin "+") (pinfunction "+_+") (pintype "passive"))
      (node (ref "U1") (pin "19") (pinfunction "VCC_19") (pintype "power_in"))
    )
    (net (code "52") (name "VUSB") (class "Default")
      (node (ref "C18") (pin "2") (pinfunction "2_2") (pintype "passive"))
      (node (ref "C6") (pin "1") (pinfunction "1_1") (pintype "passive"))
      (node (ref "D4") (pin "-") (pinfunction "-_-") (pintype "passive"))
      (node (ref "F1") (pin "2") (pinfunction "2_2") (pintype "bidirectional"))
      (node (ref "K1") (pin "2") (pinfunction "2_2") (pintype "bidirectional"))
      (node (ref "Q1") (pin "2") (pinfunction "S_2") (pintype "passive"))
      (node (ref "R11") (pin "1") (pinfunction "1_1") (pintype "passive"))
      (node (ref "U3") (pin "5") (pinfunction "VCC_5") (pintype "bidirectional"))
      (node (ref "U5") (pin "1") (pinfunction "IN_1") (pintype "bidirectional"))
      (node (ref "VUSB") (pin "T") (pinfunction "T_T") (pintype "bidirectional"))
    )
    (net (code "53") (name "unconnected-(J1-ID-Pad4)") (class "Default")
      (node (ref "J1") (pin "4") (pinfunction "ID_4") (pintype "bidirectional"))
    )
    (net (code "54") (name "unconnected-(U1-ACT#-Pad2)") (class "Default")
      (node (ref "U1") (pin "2") (pinfunction "ACT#_2") (pintype "output"))
    )
    (net (code "55") (name "unconnected-(U1-CKO-Pad1)") (class "Default")
      (node (ref "U1") (pin "1") (pinfunction "CKO_1") (pintype "output"))
    )
    (net (code "56") (name "unconnected-(U1-CTS#-Pad11)") (class "Default")
      (node (ref "U1") (pin "11") (pinfunction "CTS#_11") (pintype "input"))
    )
    (net (code "57") (name "unconnected-(U1-DCD#-Pad14)") (class "Default")
      (node (ref "U1") (pin "14") (pinfunction "DCD#_14") (pintype "input"))
    )
    (net (code "58") (name "unconnected-(U1-DSR#-Pad12)") (class "Default")
      (node (ref "U1") (pin "12") (pinfunction "DSR#_12") (pintype "input"))
    )
    (net (code "59") (name "unconnected-(U1-NC-Pad17)") (class "Default")
      (node (ref "U1") (pin "17") (pinfunction "NC_17") (pintype "no_connect"))
    )
    (net (code "60") (name "unconnected-(U1-R232-Pad18)") (class "Default")
      (node (ref "U1") (pin "18") (pinfunction "R232_18") (pintype "input"))
    )
    (net (code "61") (name "unconnected-(U1-RI#-Pad13)") (class "Default")
      (node (ref "U1") (pin "13") (pinfunction "RI#_13") (pintype "input"))
    )
    (net (code "62") (name "unconnected-(U1-RTS#-Pad16)") (class "Default")
      (node (ref "U1") (pin "16") (pinfunction "RTS#_16") (pintype "output"))
    )
    (net (code "63") (name "unconnected-(U2-ADC6-Pad19)") (class "Default")
      (node (ref "U2") (pin "19") (pinfunction "ADC6_19") (pintype "bidirectional"))
    )
    (net (code "64") (name "unconnected-(U2-ADC7-Pad22)") (class "Default")
      (node (ref "U2") (pin "22") (pinfunction "ADC7_22") (pintype "bidirectional"))
    )
    (net (code "65") (name "unconnected-(U2-PB0(ICP)-Pad12)") (class "Default")
      (node (ref "U2") (pin "12") (pinfunction "PB0(ICP)_12") (pintype "bidirectional"))
    )
    (net (code "66") (name "unconnected-(U2-PB1(OC1A)-Pad13)") (class "Default")
      (node (ref "U2") (pin "13") (pinfunction "PB1(OC1A)_13") (pintype "bidirectional"))
    )
    (net (code "67") (name "unconnected-(U2-PD4(XCK{slash}T0)-Pad2)") (class "Default")
      (node (ref "U2") (pin "2") (pinfunction "PD4(XCK/T0)_2") (pintype "bidirectional"))
    )
    (net (code "68") (name "unconnected-(U2-PD7(AIN1)-Pad11)") (class "Default")
      (node (ref "U2") (pin "11") (pinfunction "PD7(AIN1)_11") (pintype "bidirectional"))
    )
    (net (code "69") (name "unconnected-(U5-LED-Pad7)") (class "Default")
      (node (ref "U5") (pin "7") (pinfunction "LED_7") (pintype "bidirectional"))
    )
  )
)
